# Oscar_MainBoard_Analog.net
KiCad netlist of a schematic drawn in Altium Designer
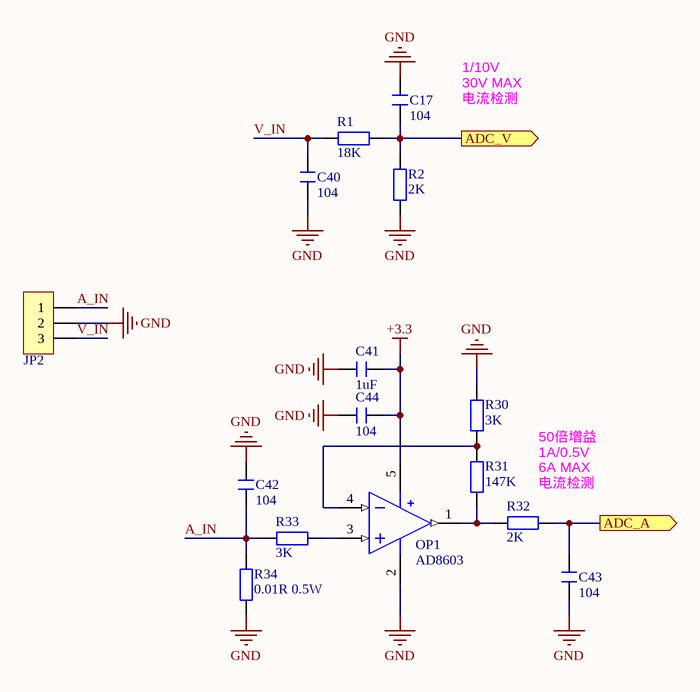
[diagram p0: Oscar_MainBoard_Analog.SchDoc]

(export (version "E")
  (design (tool "Eeschema 10.0.6"))
  (components
    (comp (ref "C17")
      (value "104")
      (footprint "C 0402_L")
      (description "贴片电容")
      (libsource (lib "0.1 - 电阻-电容-电感") (part "C"))
    )
    (comp (ref "C40")
      (value "104")
      (footprint "C 0402_L")
      (description "贴片电容")
      (libsource (lib "0.1 - 电阻-电容-电感") (part "C"))
    )
    (comp (ref "C41")
      (value "1uF")
      (footprint "C 0402_L")
      (description "贴片电容")
      (libsource (lib "0.1 - 电阻-电容-电感") (part "C"))
    )
    (comp (ref "C42")
      (value "104")
      (footprint "C 0402_L")
      (description "贴片电容")
      (libsource (lib "0.1 - 电阻-电容-电感") (part "C"))
    )
    (comp (ref "C43")
      (value "104")
      (footprint "C 0402_L")
      (description "贴片电容")
      (libsource (lib "0.1 - 电阻-电容-电感") (part "C"))
    )
    (comp (ref "C44")
      (value "104")
      (footprint "C 0402_L")
      (description "贴片电容")
      (libsource (lib "0.1 - 电阻-电容-电感") (part "C"))
    )
    (comp (ref "JP2")
      (value "HDR-1X3")
      (footprint "MX 1.25-WS-3P")
      (description "3P接插件")
      (libsource (lib "5.0 - 接插件-脚距1.25") (part "Header 3"))
    )
    (comp (ref "OP1")
      (value "AD8603")
      (footprint "SOT23-5N")
      (description "精密低功耗轨对轨")
      (libsource (lib "OpAmp比较器") (part "AD8603"))
    )
    (comp (ref "R1")
      (value "18K")
      (footprint "R 0402_L")
      (description "贴片电阻")
      (libsource (lib "0.1 - 电阻-电容-电感") (part "R"))
    )
    (comp (ref "R2")
      (value "2K")
      (footprint "R 0402_L")
      (description "贴片电阻")
      (libsource (lib "0.1 - 电阻-电容-电感") (part "R"))
    )
    (comp (ref "R30")
      (value "3K")
      (footprint "R 0402_L")
      (description "贴片电阻")
      (libsource (lib "0.1 - 电阻-电容-电感") (part "R"))
    )
    (comp (ref "R31")
      (value "147K")
      (footprint "R 0402_L")
      (description "贴片电阻")
      (libsource (lib "0.1 - 电阻-电容-电感") (part "R"))
    )
    (comp (ref "R32")
      (value "2K")
      (footprint "R 0402_L")
      (description "贴片电阻")
      (libsource (lib "0.1 - 电阻-电容-电感") (part "R"))
    )
    (comp (ref "R33")
      (value "3K")
      (footprint "R 0402_L")
      (description "贴片电阻")
      (libsource (lib "0.1 - 电阻-电容-电感") (part "R"))
    )
    (comp (ref "R34")
      (value "0.01R 0.5W")
      (footprint "R 0805_L")
      (description "贴片电阻")
      (libsource (lib "0.1 - 电阻-电容-电感") (part "R"))
    )
  )
  (nets
    (net (code "1") (name "+3.3") (class "Default")
      (node (ref "C41") (pin "1") (pinfunction "1_1") (pintype "passive"))
      (node (ref "C44") (pin "1") (pinfunction "1_1") (pintype "passive"))
      (node (ref "OP1") (pin "5") (pinfunction "VCC_5") (pintype "power_in"))
    )
    (net (code "2") (name "/ADC_A") (class "Default")
      (node (ref "C43") (pin "1") (pinfunction "1_1") (pintype "passive"))
      (node (ref "R32") (pin "1") (pinfunction "1_1") (pintype "passive"))
    )
    (net (code "3") (name "/ADC_V") (class "Default")
      (node (ref "C17") (pin "2") (pinfunction "2_2") (pintype "passive"))
      (node (ref "R1") (pin "2") (pinfunction "2_2") (pintype "passive"))
      (node (ref "R2") (pin "1") (pinfunction "1_1") (pintype "passive"))
    )
    (net (code "4") (name "/A_IN") (class "Default")
      (node (ref "C42") (pin "2") (pinfunction "2_2") (pintype "passive"))
      (node (ref "JP2") (pin "1") (pinfunction "1_1") (pintype "passive"))
      (node (ref "R33") (pin "1") (pinfunction "1_1") (pintype "passive"))
      (node (ref "R34") (pin "1") (pinfunction "1_1") (pintype "passive"))
    )
    (net (code "5") (name "/V_IN") (class "Default")
      (node (ref "C40") (pin "1") (pinfunction "1_1") (pintype "passive"))
      (node (ref "JP2") (pin "3") (pinfunction "3_3") (pintype "passive"))
      (node (ref "R1") (pin "1") (pinfunction "1_1") (pintype "passive"))
    )
    (net (code "6") (name "GND") (class "Default")
      (node (ref "C17") (pin "1") (pinfunction "1_1") (pintype "passive"))
      (node (ref "C40") (pin "2") (pinfunction "2_2") (pintype "passive"))
      (node (ref "C41") (pin "2") (pinfunction "2_2") (pintype "passive"))
      (node (ref "C42") (pin "1") (pinfunction "1_1") (pintype "passive"))
      (node (ref "C43") (pin "2") (pinfunction "2_2") (pintype "passive"))
      (node (ref "C44") (pin "2") (pinfunction "2_2") (pintype "passive"))
      (node (ref "JP2") (pin "2") (pinfunction "2_2") (pintype "passive"))
      (node (ref "OP1") (pin "2") (pinfunction "VEE_2") (pintype "power_in"))
      (node (ref "R2") (pin "2") (pinfunction "2_2") (pintype "passive"))
      (node (ref "R30") (pin "2") (pinfunction "2_2") (pintype "passive"))
      (node (ref "R34") (pin "2") (pinfunction "2_2") (pintype "passive"))
    )
    (net (code "7") (name "Net-(OP1-IN+)") (class "Default")
      (node (ref "OP1") (pin "3") (pinfunction "IN+_3") (pintype "input"))
      (node (ref "R33") (pin "2") (pinfunction "2_2") (pintype "passive"))
    )
    (net (code "8") (name "Net-(OP1-IN-)") (class "Default")
      (node (ref "OP1") (pin "4") (pinfunction "IN-_4") (pintype "input"))
      (node (ref "R30") (pin "1") (pinfunction "1_1") (pintype "passive"))
      (node (ref "R31") (pin "2") (pinfunction "2_2") (pintype "passive"))
    )
    (net (code "9") (name "Net-(OP1-OUT)") (class "Default")
      (node (ref "OP1") (pin "1") (pinfunction "OUT_1") (pintype "output"))
      (node (ref "R31") (pin "1") (pinfunction "1_1") (pintype "passive"))
      (node (ref "R32") (pin "2") (pinfunction "2_2") (pintype "passive"))
    )
  )
)
